# light_v2.net
KiCad netlist of a schematic drawn in EAGLE
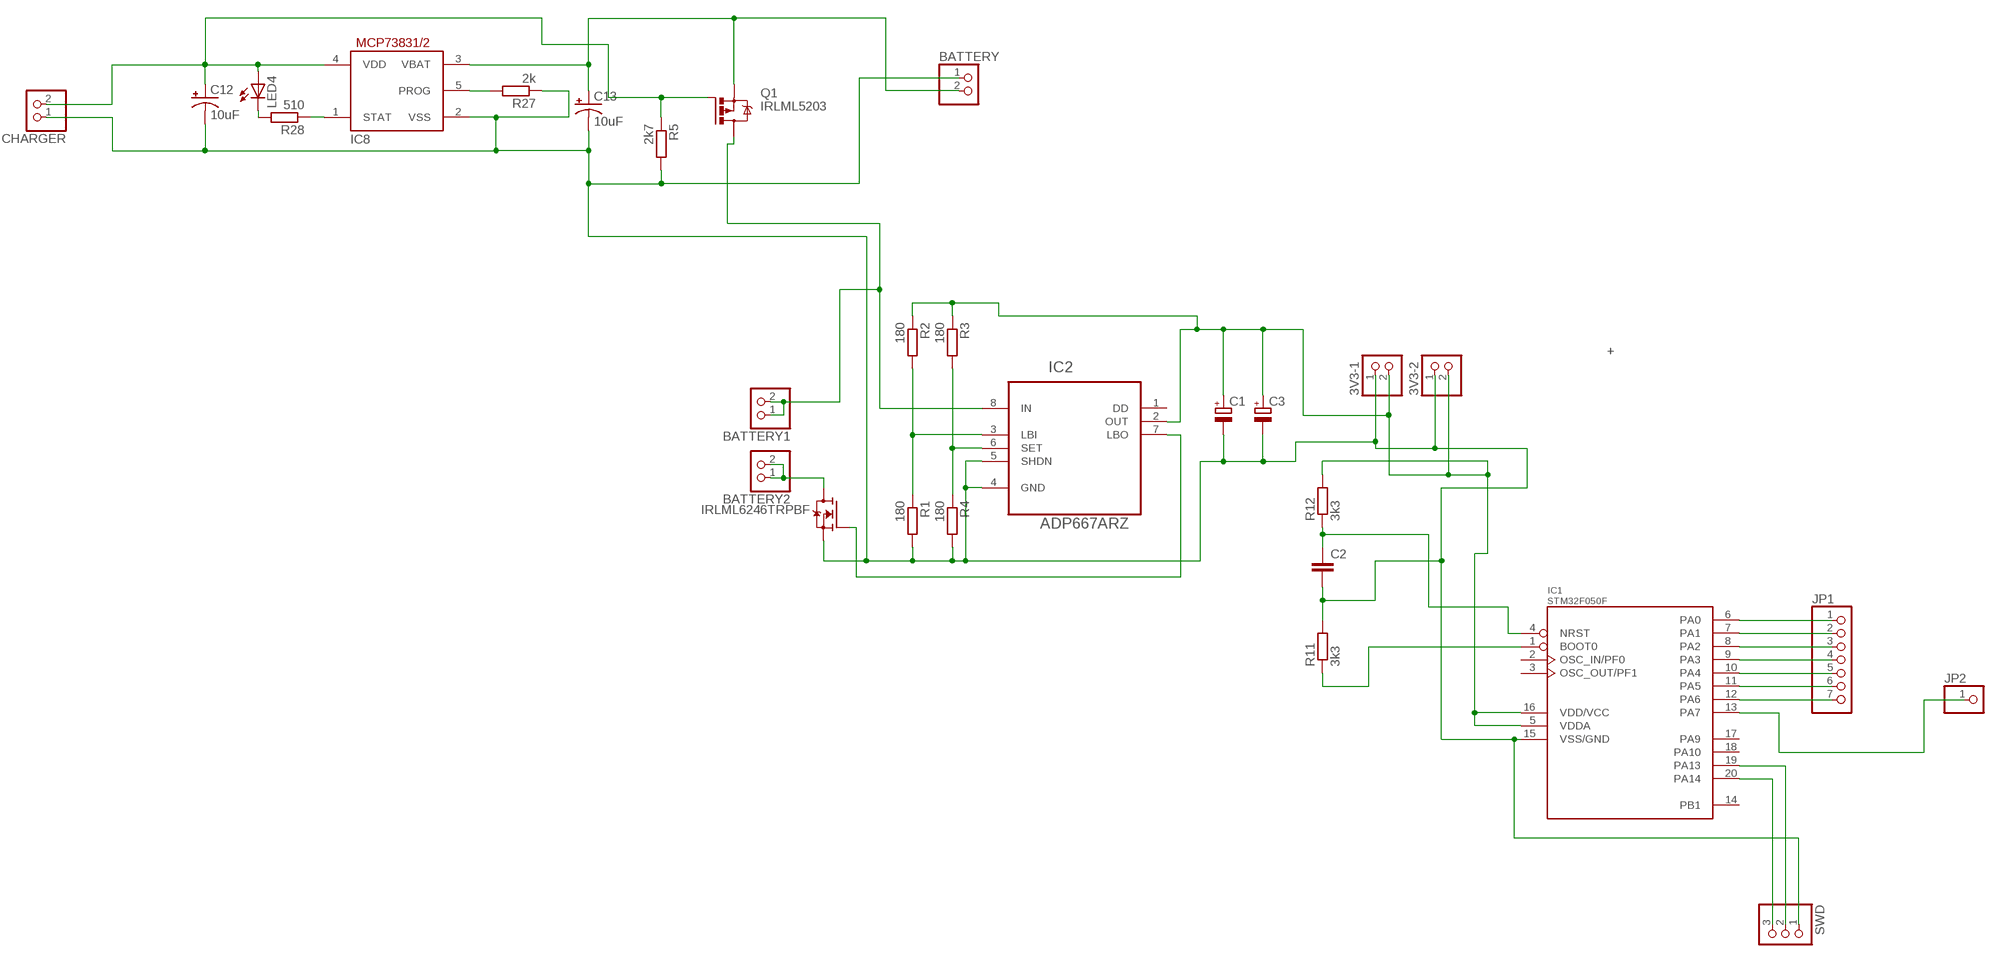
[diagram p0: schematic, sheet 1]

(export (version "E")
  (design (tool "Eeschema 10.0.6"))
  (components
    (comp (ref "3V3-1")
      (value "PINHD-1X2")
      (footprint "eagle-import:1X02")
      (libsource (lib "eagle-import") (part "PINHD-1X2"))
    )
    (comp (ref "3V3-2")
      (value "PINHD-1X2")
      (footprint "eagle-import:1X02")
      (libsource (lib "eagle-import") (part "PINHD-1X2"))
    )
    (comp (ref "BATTERY")
      (value "PINHD-1X2")
      (footprint "eagle-import:1X02")
      (libsource (lib "eagle-import") (part "PINHD-1X2"))
    )
    (comp (ref "BATTERY1")
      (value "PINHD-1X2")
      (footprint "eagle-import:1X02")
      (libsource (lib "eagle-import") (part "PINHD-1X2"))
    )
    (comp (ref "BATTERY2")
      (value "PINHD-1X2")
      (footprint "eagle-import:1X02")
      (libsource (lib "eagle-import") (part "PINHD-1X2"))
    )
    (comp (ref "C1")
      (value "CPOL-EUSMCD")
      (footprint "eagle-import:SMC_D")
      (libsource (lib "eagle-import") (part "CPOL-EUSMCD"))
    )
    (comp (ref "C2")
      (value "C-EUC1206")
      (footprint "eagle-import:C1206")
      (libsource (lib "eagle-import") (part "C-EUC1206"))
    )
    (comp (ref "C3")
      (value "CPOL-EUSMCD")
      (footprint "eagle-import:SMC_D")
      (libsource (lib "eagle-import") (part "CPOL-EUSMCD"))
    )
    (comp (ref "C12")
      (value "10uF")
      (footprint "eagle-import:SMC_D")
      (libsource (lib "eagle-import") (part "CPOL-USSMCD"))
    )
    (comp (ref "C13")
      (value "10uF")
      (footprint "eagle-import:SMC_D")
      (libsource (lib "eagle-import") (part "CPOL-USSMCD"))
    )
    (comp (ref "CHARGER")
      (value "PINHD-1X2")
      (footprint "eagle-import:1X02")
      (libsource (lib "eagle-import") (part "PINHD-1X2"))
    )
    (comp (ref "IC1")
      (value "STM32F050F")
      (footprint "eagle-import:TSSOP20")
      (libsource (lib "eagle-import") (part "STM32F050F"))
    )
    (comp (ref "IC2")
      (value "ADP667ARZ")
      (footprint "eagle-import:SOIC127P600X175-8N")
      (libsource (lib "eagle-import") (part "ADP667ARZ"))
    )
    (comp (ref "IC8")
      (value "MCP73831/OT")
      (footprint "eagle-import:SOT23-5L")
      (libsource (lib "eagle-import") (part "MCP73831/OT"))
    )
    (comp (ref "IRLML6246TRPBF")
      (value "MOSFET-N-SOT23")
      (footprint "eagle-import:SOT23")
      (libsource (lib "eagle-import") (part "MOSFET-N-SOT23"))
    )
    (comp (ref "JP1")
      (value "PINHD-1X7")
      (footprint "eagle-import:1X07")
      (libsource (lib "eagle-import") (part "PINHD-1X7"))
    )
    (comp (ref "JP2")
      (value "PINHD-1X1")
      (footprint "eagle-import:1X01")
      (libsource (lib "eagle-import") (part "PINHD-1X1"))
    )
    (comp (ref "LED4")
      (value "LED")
      (footprint "eagle-import:SMARTLED-TTW")
      (libsource (lib "eagle-import") (part "LED"))
    )
    (comp (ref "Q1")
      (value "IRLML5203")
      (footprint "eagle-import:MICRO3")
      (libsource (lib "eagle-import") (part "IRLML5203"))
    )
    (comp (ref "R1")
      (value "180")
      (footprint "eagle-import:M1206")
      (libsource (lib "eagle-import") (part "R-EU_M1206"))
    )
    (comp (ref "R2")
      (value "180")
      (footprint "eagle-import:M1206")
      (libsource (lib "eagle-import") (part "R-EU_M1206"))
    )
    (comp (ref "R3")
      (value "180")
      (footprint "eagle-import:M1206")
      (libsource (lib "eagle-import") (part "R-EU_M1206"))
    )
    (comp (ref "R4")
      (value "180")
      (footprint "eagle-import:M1206")
      (libsource (lib "eagle-import") (part "R-EU_M1206"))
    )
    (comp (ref "R5")
      (value "2k7")
      (footprint "eagle-import:M1206")
      (libsource (lib "eagle-import") (part "R-EU_M1206"))
    )
    (comp (ref "R11")
      (value "3k3")
      (footprint "eagle-import:M1206")
      (libsource (lib "eagle-import") (part "R-EU_M1206"))
    )
    (comp (ref "R12")
      (value "3k3")
      (footprint "eagle-import:M1206")
      (libsource (lib "eagle-import") (part "R-EU_M1206"))
    )
    (comp (ref "R27")
      (value "2k")
      (footprint "eagle-import:M1206")
      (libsource (lib "eagle-import") (part "R-EU_M1206"))
    )
    (comp (ref "R28")
      (value "510")
      (footprint "eagle-import:M1206")
      (libsource (lib "eagle-import") (part "R-EU_M1206"))
    )
    (comp (ref "SWD")
      (value "PINHD-1X3")
      (footprint "eagle-import:1X03")
      (libsource (lib "eagle-import") (part "PINHD-1X3"))
    )
  )
  (nets
    (net (code "1") (name "Net-(IC1-BOOT0)") (class "Default")
      (node (ref "IC1") (pin "1") (pinfunction "BOOT0_1") (pintype "bidirectional"))
      (node (ref "R11") (pin "1") (pinfunction "1_1") (pintype "passive"))
    )
    (net (code "2") (name "Net-(IC1-NRST)") (class "Default")
      (node (ref "C2") (pin "1") (pinfunction "1_1") (pintype "passive"))
      (node (ref "IC1") (pin "4") (pinfunction "NRST_4") (pintype "bidirectional"))
      (node (ref "R12") (pin "1") (pinfunction "1_1") (pintype "passive"))
    )
    (net (code "3") (name "Net-(IC1-PA0)") (class "Default")
      (node (ref "IC1") (pin "6") (pinfunction "PA0_6") (pintype "bidirectional"))
      (node (ref "JP1") (pin "1") (pinfunction "1_1") (pintype "passive"))
    )
    (net (code "4") (name "Net-(IC1-PA1)") (class "Default")
      (node (ref "IC1") (pin "7") (pinfunction "PA1_7") (pintype "bidirectional"))
      (node (ref "JP1") (pin "2") (pinfunction "2_2") (pintype "passive"))
    )
    (net (code "5") (name "Net-(IC1-PA2)") (class "Default")
      (node (ref "IC1") (pin "8") (pinfunction "PA2_8") (pintype "bidirectional"))
      (node (ref "JP1") (pin "3") (pinfunction "3_3") (pintype "passive"))
    )
    (net (code "6") (name "Net-(IC1-PA3)") (class "Default")
      (node (ref "IC1") (pin "9") (pinfunction "PA3_9") (pintype "bidirectional"))
      (node (ref "JP1") (pin "4") (pinfunction "4_4") (pintype "passive"))
    )
    (net (code "7") (name "Net-(IC1-PA4)") (class "Default")
      (node (ref "IC1") (pin "10") (pinfunction "PA4_10") (pintype "bidirectional"))
      (node (ref "JP1") (pin "5") (pinfunction "5_5") (pintype "passive"))
    )
    (net (code "8") (name "Net-(IC1-PA5)") (class "Default")
      (node (ref "IC1") (pin "11") (pinfunction "PA5_11") (pintype "bidirectional"))
      (node (ref "JP1") (pin "6") (pinfunction "6_6") (pintype "passive"))
    )
    (net (code "9") (name "Net-(IC1-PA6)") (class "Default")
      (node (ref "IC1") (pin "12") (pinfunction "PA6_12") (pintype "bidirectional"))
      (node (ref "JP1") (pin "7") (pinfunction "7_7") (pintype "passive"))
    )
    (net (code "10") (name "Net-(IC1-PA7)") (class "Default")
      (node (ref "IC1") (pin "13") (pinfunction "PA7_13") (pintype "bidirectional"))
      (node (ref "JP2") (pin "1") (pinfunction "1_1") (pintype "passive"))
    )
    (net (code "11") (name "Net-(IC1-PA13)") (class "Default")
      (node (ref "IC1") (pin "19") (pinfunction "PA13_19") (pintype "bidirectional"))
      (node (ref "SWD") (pin "2") (pinfunction "2_2") (pintype "passive"))
    )
    (net (code "12") (name "Net-(IC1-PA14)") (class "Default")
      (node (ref "IC1") (pin "20") (pinfunction "PA14_20") (pintype "bidirectional"))
      (node (ref "SWD") (pin "3") (pinfunction "3_3") (pintype "passive"))
    )
    (net (code "13") (name "Net-(IC1-VDDA)") (class "Default")
      (node (ref "3V3-1") (pin "2") (pinfunction "2_2") (pintype "passive"))
      (node (ref "3V3-2") (pin "2") (pinfunction "2_2") (pintype "passive"))
      (node (ref "C1") (pin "+") (pinfunction "+_+") (pintype "passive"))
      (node (ref "C3") (pin "+") (pinfunction "+_+") (pintype "passive"))
      (node (ref "IC1") (pin "16") (pinfunction "VDD/VCC_16") (pintype "power_in"))
      (node (ref "IC1") (pin "5") (pinfunction "VDDA_5") (pintype "power_in"))
      (node (ref "IC2") (pin "2") (pinfunction "OUT_2") (pintype "output"))
      (node (ref "R12") (pin "2") (pinfunction "2_2") (pintype "passive"))
      (node (ref "R2") (pin "1") (pinfunction "1_1") (pintype "passive"))
      (node (ref "R3") (pin "1") (pinfunction "1_1") (pintype "passive"))
    )
    (net (code "14") (name "Net-(IC1-VSS{slash}GND)") (class "Default")
      (node (ref "3V3-1") (pin "1") (pinfunction "1_1") (pintype "passive"))
      (node (ref "3V3-2") (pin "1") (pinfunction "1_1") (pintype "passive"))
      (node (ref "BATTERY") (pin "1") (pinfunction "1_1") (pintype "passive"))
      (node (ref "C1") (pin "-") (pinfunction "-_-") (pintype "passive"))
      (node (ref "C12") (pin "-") (pinfunction "-_-") (pintype "passive"))
      (node (ref "C13") (pin "-") (pinfunction "-_-") (pintype "passive"))
      (node (ref "C2") (pin "2") (pinfunction "2_2") (pintype "passive"))
      (node (ref "C3") (pin "-") (pinfunction "-_-") (pintype "passive"))
      (node (ref "CHARGER") (pin "1") (pinfunction "1_1") (pintype "passive"))
      (node (ref "IC1") (pin "15") (pinfunction "VSS/GND_15") (pintype "power_in"))
      (node (ref "IC2") (pin "4") (pinfunction "GND_4") (pintype "passive"))
      (node (ref "IC2") (pin "5") (pinfunction "SHDN_5") (pintype "input"))
      (node (ref "IC8") (pin "2") (pinfunction "VSS_2") (pintype "power_in"))
      (node (ref "IRLML6246TRPBF") (pin "2") (pinfunction "S_2") (pintype "passive"))
      (node (ref "R1") (pin "2") (pinfunction "2_2") (pintype "passive"))
      (node (ref "R11") (pin "2") (pinfunction "2_2") (pintype "passive"))
      (node (ref "R27") (pin "1") (pinfunction "1_1") (pintype "passive"))
      (node (ref "R4") (pin "2") (pinfunction "2_2") (pintype "passive"))
      (node (ref "R5") (pin "2") (pinfunction "2_2") (pintype "passive"))
      (node (ref "SWD") (pin "1") (pinfunction "1_1") (pintype "passive"))
    )
    (net (code "15") (name "Net-(IC2-IN)") (class "Default")
      (node (ref "BATTERY1") (pin "1") (pinfunction "1_1") (pintype "passive"))
      (node (ref "BATTERY1") (pin "2") (pinfunction "2_2") (pintype "passive"))
      (node (ref "IC2") (pin "8") (pinfunction "IN_8") (pintype "input"))
      (node (ref "Q1") (pin "3") (pinfunction "D_3") (pintype "passive"))
    )
    (net (code "16") (name "Net-(IC2-LBI)") (class "Default")
      (node (ref "IC2") (pin "3") (pinfunction "LBI_3") (pintype "input"))
      (node (ref "R1") (pin "1") (pinfunction "1_1") (pintype "passive"))
      (node (ref "R2") (pin "2") (pinfunction "2_2") (pintype "passive"))
    )
    (net (code "17") (name "Net-(IC2-LBO)") (class "Default")
      (node (ref "IC2") (pin "7") (pinfunction "LBO_7") (pintype "output"))
      (node (ref "IRLML6246TRPBF") (pin "1") (pinfunction "G_1") (pintype "passive"))
    )
    (net (code "18") (name "Net-(IC2-SET)") (class "Default")
      (node (ref "IC2") (pin "6") (pinfunction "SET_6") (pintype "input"))
      (node (ref "R3") (pin "2") (pinfunction "2_2") (pintype "passive"))
      (node (ref "R4") (pin "1") (pinfunction "1_1") (pintype "passive"))
    )
    (net (code "19") (name "Net-(IC8-PROG)") (class "Default")
      (node (ref "IC8") (pin "5") (pinfunction "PROG_5") (pintype "input"))
      (node (ref "R27") (pin "2") (pinfunction "2_2") (pintype "passive"))
    )
    (net (code "20") (name "Net-(IC8-STAT)") (class "Default")
      (node (ref "IC8") (pin "1") (pinfunction "STAT_1") (pintype "output"))
      (node (ref "R28") (pin "1") (pinfunction "1_1") (pintype "passive"))
    )
    (net (code "21") (name "Net-(IC8-VBAT)") (class "Default")
      (node (ref "BATTERY") (pin "2") (pinfunction "2_2") (pintype "passive"))
      (node (ref "C13") (pin "+") (pinfunction "+_+") (pintype "passive"))
      (node (ref "IC8") (pin "3") (pinfunction "VBAT_3") (pintype "bidirectional"))
      (node (ref "Q1") (pin "2") (pinfunction "S_2") (pintype "passive"))
    )
    (net (code "22") (name "Net-(IC8-VDD)") (class "Default")
      (node (ref "C12") (pin "+") (pinfunction "+_+") (pintype "passive"))
      (node (ref "CHARGER") (pin "2") (pinfunction "2_2") (pintype "passive"))
      (node (ref "IC8") (pin "4") (pinfunction "VDD_4") (pintype "power_in"))
      (node (ref "LED4") (pin "A@1") (pinfunction "A_A@1") (pintype "passive"))
      (node (ref "Q1") (pin "1") (pinfunction "G_1") (pintype "passive"))
      (node (ref "R5") (pin "1") (pinfunction "1_1") (pintype "passive"))
    )
    (net (code "23") (name "Net-(IRLML6246TRPBF-D)") (class "Default")
      (node (ref "BATTERY2") (pin "1") (pinfunction "1_1") (pintype "passive"))
      (node (ref "BATTERY2") (pin "2") (pinfunction "2_2") (pintype "passive"))
      (node (ref "IRLML6246TRPBF") (pin "3") (pinfunction "D_3") (pintype "passive"))
    )
    (net (code "24") (name "Net-(LED4-C)") (class "Default")
      (node (ref "LED4") (pin "C@1") (pinfunction "C_C@1") (pintype "passive"))
      (node (ref "R28") (pin "2") (pinfunction "2_2") (pintype "passive"))
    )
    (net (code "25") (name "unconnected-(IC1-OSC_IN{slash}PF0-Pad2)") (class "Default")
      (node (ref "IC1") (pin "2") (pinfunction "OSC_IN/PF0_2") (pintype "bidirectional"))
    )
    (net (code "26") (name "unconnected-(IC1-OSC_OUT{slash}PF1-Pad3)") (class "Default")
      (node (ref "IC1") (pin "3") (pinfunction "OSC_OUT/PF1_3") (pintype "bidirectional"))
    )
    (net (code "27") (name "unconnected-(IC1-PA9-Pad17)") (class "Default")
      (node (ref "IC1") (pin "17") (pinfunction "PA9_17") (pintype "bidirectional"))
    )
    (net (code "28") (name "unconnected-(IC1-PA10-Pad18)") (class "Default")
      (node (ref "IC1") (pin "18") (pinfunction "PA10_18") (pintype "bidirectional"))
    )
    (net (code "29") (name "unconnected-(IC1-PB1-Pad14)") (class "Default")
      (node (ref "IC1") (pin "14") (pinfunction "PB1_14") (pintype "bidirectional"))
    )
    (net (code "30") (name "unconnected-(IC2-DD-Pad1)") (class "Default")
      (node (ref "IC2") (pin "1") (pinfunction "DD_1") (pintype "output"))
    )
  )
)
